# LPC82X_TSSOP_breadboard_mini.net
KiCad netlist of a schematic drawn in EAGLE
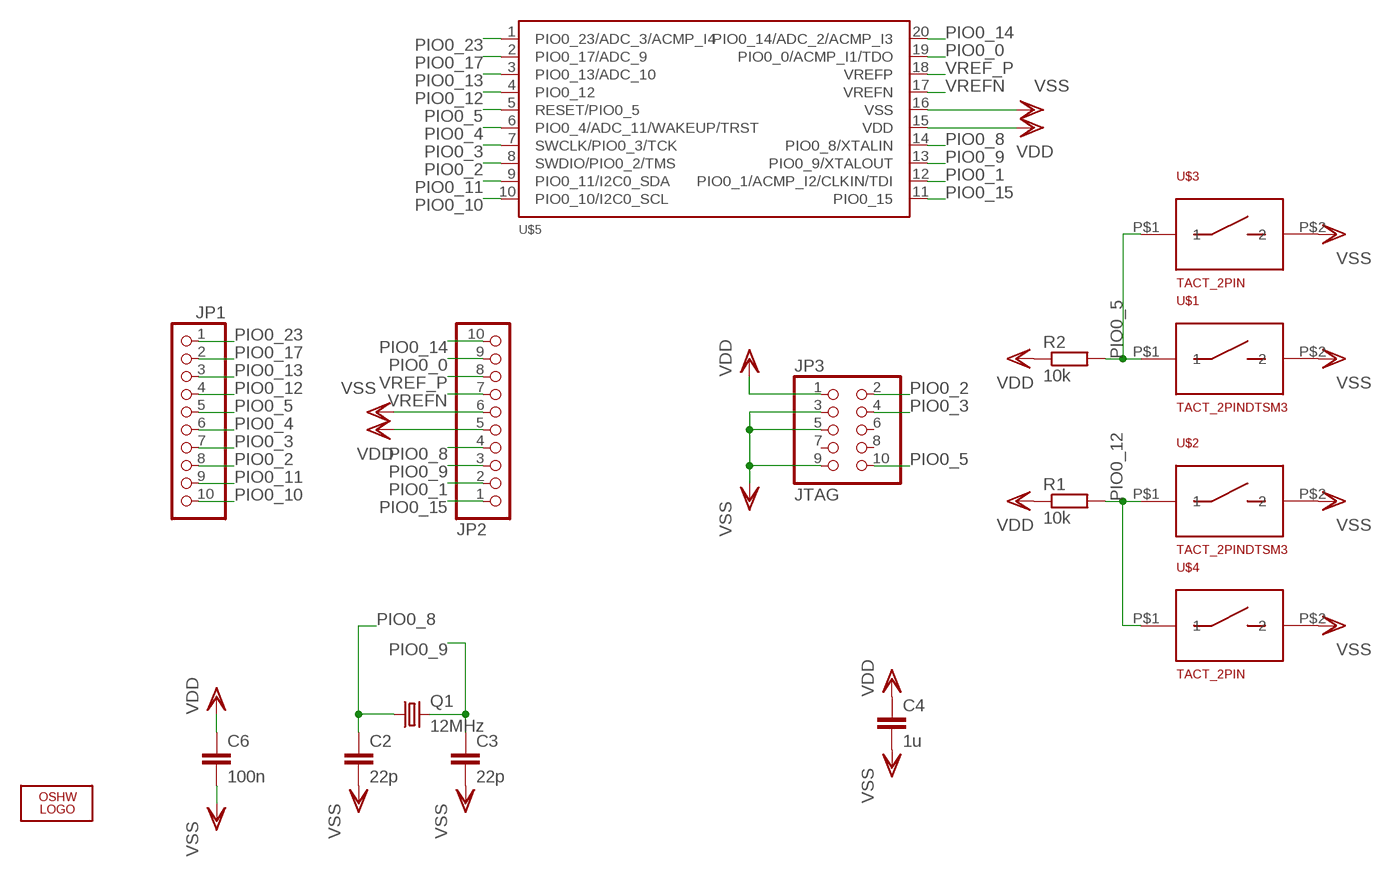
[diagram p0: schematic, sheet 1]

(export (version "E")
  (design (tool "Eeschema 10.0.6"))
  (components
    (comp (ref "C2")
      (value "22p")
      (footprint "eagle-import:C0603K")
      (libsource (lib "eagle-import") (part "C-EUC0603K"))
    )
    (comp (ref "C3")
      (value "22p")
      (footprint "eagle-import:C0603K")
      (libsource (lib "eagle-import") (part "C-EUC0603K"))
    )
    (comp (ref "C4")
      (value "1u")
      (footprint "eagle-import:C0805K")
      (libsource (lib "eagle-import") (part "bart_rcl_C-EUC0805K"))
    )
    (comp (ref "C6")
      (value "100n")
      (footprint "eagle-import:C0603K")
      (libsource (lib "eagle-import") (part "C-EUC0603K"))
    )
    (comp (ref "JP1")
      (value "PINHD-1X10NORM_OCT")
      (footprint "eagle-import:1X10_NORMAL_OCT")
      (libsource (lib "eagle-import") (part "PINHD-1X10NORM_OCT"))
    )
    (comp (ref "JP2")
      (value "PINHD-1X10NORM_OCT")
      (footprint "eagle-import:1X10_NORMAL_OCT")
      (libsource (lib "eagle-import") (part "PINHD-1X10NORM_OCT"))
    )
    (comp (ref "JP3")
      (value "JTAG")
      (footprint "eagle-import:2X05_1.27_SMD")
      (libsource (lib "eagle-import") (part "PINHD-2X5SMD_1.27_SMD"))
    )
    (comp (ref "LOGO2")
      (value "OSHW_LOGO_FILLX0150-NT")
      (footprint "eagle-import:OSHW_FILLX150_NOTEXT")
      (libsource (lib "eagle-import") (part "OSHW_LOGO_FILLX0150-NT"))
    )
    (comp (ref "Q1")
      (value "12MHz")
      (footprint "eagle-import:CRYSTAL_5.0X3.2")
      (libsource (lib "eagle-import") (part "CRYSTALSMD_5.0X3.2"))
    )
    (comp (ref "R1")
      (value "10k")
      (footprint "eagle-import:R0603")
      (libsource (lib "eagle-import") (part "R-EU_R0603"))
    )
    (comp (ref "R2")
      (value "10k")
      (footprint "eagle-import:R0603")
      (libsource (lib "eagle-import") (part "R-EU_R0603"))
    )
    (comp (ref "U$1")
      (value "TACT_2PINDTSM3")
      (footprint "eagle-import:DTSM3")
      (libsource (lib "eagle-import") (part "TACT_2PINDTSM3"))
    )
    (comp (ref "U$2")
      (value "TACT_2PINDTSM3")
      (footprint "eagle-import:DTSM3")
      (libsource (lib "eagle-import") (part "TACT_2PINDTSM3"))
    )
    (comp (ref "U$3")
      (value "TACT_2PIN")
      (footprint "eagle-import:TD-85XU")
      (libsource (lib "eagle-import") (part "TACT_2PIN"))
    )
    (comp (ref "U$4")
      (value "TACT_2PIN")
      (footprint "eagle-import:TD-85XU")
      (libsource (lib "eagle-import") (part "TACT_2PIN"))
    )
    (comp (ref "U$5")
      (value "LPC82XM101JDH20")
      (footprint "eagle-import:TSSOP20")
      (libsource (lib "eagle-import") (part "LPC82XM101JDH20"))
    )
  )
  (nets
    (net (code "1") (name "/PIO0_0") (class "Default")
      (node (ref "JP2") (pin "9") (pinfunction "9_9") (pintype "passive"))
      (node (ref "U$5") (pin "19") (pinfunction "PIO0_0/ACMP_I1/TDO_19") (pintype "bidirectional"))
    )
    (net (code "2") (name "/PIO0_1") (class "Default")
      (node (ref "JP2") (pin "2") (pinfunction "2_2") (pintype "passive"))
      (node (ref "U$5") (pin "12") (pinfunction "PIO0_1/ACMP_I2/CLKIN/TDI_12") (pintype "bidirectional"))
    )
    (net (code "3") (name "/PIO0_2") (class "Default")
      (node (ref "JP1") (pin "8") (pinfunction "8_8") (pintype "passive"))
      (node (ref "JP3") (pin "2") (pinfunction "2_2") (pintype "passive"))
      (node (ref "U$5") (pin "8") (pinfunction "SWDIO/PIO0_2/TMS_8") (pintype "bidirectional"))
    )
    (net (code "4") (name "/PIO0_3") (class "Default")
      (node (ref "JP1") (pin "7") (pinfunction "7_7") (pintype "passive"))
      (node (ref "JP3") (pin "4") (pinfunction "4_4") (pintype "passive"))
      (node (ref "U$5") (pin "7") (pinfunction "SWCLK/PIO0_3/TCK_7") (pintype "bidirectional"))
    )
    (net (code "5") (name "/PIO0_4") (class "Default")
      (node (ref "JP1") (pin "6") (pinfunction "6_6") (pintype "passive"))
      (node (ref "U$5") (pin "6") (pinfunction "PIO0_4/ADC_11/WAKEUP/TRST_6") (pintype "bidirectional"))
    )
    (net (code "6") (name "/PIO0_5") (class "Default")
      (node (ref "JP1") (pin "5") (pinfunction "5_5") (pintype "passive"))
      (node (ref "JP3") (pin "10") (pinfunction "10_10") (pintype "passive"))
      (node (ref "R2") (pin "2") (pinfunction "2_2") (pintype "passive"))
      (node (ref "U$1") (pin "P$1") (pinfunction "1_P$1") (pintype "bidirectional"))
      (node (ref "U$3") (pin "P$1") (pinfunction "1_P$1") (pintype "bidirectional"))
      (node (ref "U$5") (pin "5") (pinfunction "RESET/PIO0_5_5") (pintype "bidirectional"))
    )
    (net (code "7") (name "/PIO0_8") (class "Default")
      (node (ref "C2") (pin "1") (pinfunction "1_1") (pintype "passive"))
      (node (ref "JP2") (pin "4") (pinfunction "4_4") (pintype "passive"))
      (node (ref "Q1") (pin "1") (pinfunction "1_1") (pintype "passive"))
      (node (ref "U$5") (pin "14") (pinfunction "PIO0_8/XTALIN_14") (pintype "bidirectional"))
    )
    (net (code "8") (name "/PIO0_9") (class "Default")
      (node (ref "C3") (pin "1") (pinfunction "1_1") (pintype "passive"))
      (node (ref "JP2") (pin "3") (pinfunction "3_3") (pintype "passive"))
      (node (ref "Q1") (pin "2") (pinfunction "2_2") (pintype "passive"))
      (node (ref "U$5") (pin "13") (pinfunction "PIO0_9/XTALOUT_13") (pintype "bidirectional"))
    )
    (net (code "9") (name "/PIO0_10") (class "Default")
      (node (ref "JP1") (pin "10") (pinfunction "10_10") (pintype "passive"))
      (node (ref "U$5") (pin "10") (pinfunction "PIO0_10/I2C0_SCL_10") (pintype "bidirectional"))
    )
    (net (code "10") (name "/PIO0_11") (class "Default")
      (node (ref "JP1") (pin "9") (pinfunction "9_9") (pintype "passive"))
      (node (ref "U$5") (pin "9") (pinfunction "PIO0_11/I2C0_SDA_9") (pintype "bidirectional"))
    )
    (net (code "11") (name "/PIO0_12") (class "Default")
      (node (ref "JP1") (pin "4") (pinfunction "4_4") (pintype "passive"))
      (node (ref "R1") (pin "2") (pinfunction "2_2") (pintype "passive"))
      (node (ref "U$2") (pin "P$1") (pinfunction "1_P$1") (pintype "bidirectional"))
      (node (ref "U$4") (pin "P$1") (pinfunction "1_P$1") (pintype "bidirectional"))
      (node (ref "U$5") (pin "4") (pinfunction "PIO0_12_4") (pintype "bidirectional"))
    )
    (net (code "12") (name "/PIO0_13") (class "Default")
      (node (ref "JP1") (pin "3") (pinfunction "3_3") (pintype "passive"))
      (node (ref "U$5") (pin "3") (pinfunction "PIO0_13/ADC_10_3") (pintype "bidirectional"))
    )
    (net (code "13") (name "/PIO0_14") (class "Default")
      (node (ref "JP2") (pin "10") (pinfunction "10_10") (pintype "passive"))
      (node (ref "U$5") (pin "20") (pinfunction "PIO0_14/ADC_2/ACMP_I3_20") (pintype "bidirectional"))
    )
    (net (code "14") (name "/PIO0_15") (class "Default")
      (node (ref "JP2") (pin "1") (pinfunction "1_1") (pintype "passive"))
      (node (ref "U$5") (pin "11") (pinfunction "PIO0_15_11") (pintype "bidirectional"))
    )
    (net (code "15") (name "/PIO0_17") (class "Default")
      (node (ref "JP1") (pin "2") (pinfunction "2_2") (pintype "passive"))
      (node (ref "U$5") (pin "2") (pinfunction "PIO0_17/ADC_9_2") (pintype "bidirectional"))
    )
    (net (code "16") (name "/PIO0_23") (class "Default")
      (node (ref "JP1") (pin "1") (pinfunction "1_1") (pintype "passive"))
      (node (ref "U$5") (pin "1") (pinfunction "PIO0_23/ADC_3/ACMP_I4_1") (pintype "bidirectional"))
    )
    (net (code "17") (name "/VREFN") (class "Default")
      (node (ref "JP2") (pin "7") (pinfunction "7_7") (pintype "passive"))
      (node (ref "U$5") (pin "17") (pinfunction "VREFN_17") (pintype "bidirectional"))
    )
    (net (code "18") (name "/VREF_P") (class "Default")
      (node (ref "JP2") (pin "8") (pinfunction "8_8") (pintype "passive"))
      (node (ref "U$5") (pin "18") (pinfunction "VREFP_18") (pintype "bidirectional"))
    )
    (net (code "19") (name "VDD") (class "Default")
      (node (ref "C4") (pin "1") (pinfunction "1_1") (pintype "passive"))
      (node (ref "C6") (pin "1") (pinfunction "1_1") (pintype "passive"))
      (node (ref "JP2") (pin "5") (pinfunction "5_5") (pintype "passive"))
      (node (ref "JP3") (pin "1") (pinfunction "1_1") (pintype "passive"))
      (node (ref "R1") (pin "1") (pinfunction "1_1") (pintype "passive"))
      (node (ref "R2") (pin "1") (pinfunction "1_1") (pintype "passive"))
      (node (ref "U$5") (pin "15") (pinfunction "VDD_15") (pintype "bidirectional"))
    )
    (net (code "20") (name "VSS") (class "Default")
      (node (ref "C2") (pin "2") (pinfunction "2_2") (pintype "passive"))
      (node (ref "C3") (pin "2") (pinfunction "2_2") (pintype "passive"))
      (node (ref "C4") (pin "2") (pinfunction "2_2") (pintype "passive"))
      (node (ref "C6") (pin "2") (pinfunction "2_2") (pintype "passive"))
      (node (ref "JP2") (pin "6") (pinfunction "6_6") (pintype "passive"))
      (node (ref "JP3") (pin "3") (pinfunction "3_3") (pintype "passive"))
      (node (ref "JP3") (pin "5") (pinfunction "5_5") (pintype "passive"))
      (node (ref "JP3") (pin "9") (pinfunction "9_9") (pintype "passive"))
      (node (ref "U$1") (pin "P$2") (pinfunction "2_P$2") (pintype "bidirectional"))
      (node (ref "U$2") (pin "P$2") (pinfunction "2_P$2") (pintype "bidirectional"))
      (node (ref "U$3") (pin "P$2") (pinfunction "2_P$2") (pintype "bidirectional"))
      (node (ref "U$4") (pin "P$2") (pinfunction "2_P$2") (pintype "bidirectional"))
      (node (ref "U$5") (pin "16") (pinfunction "VSS_16") (pintype "bidirectional"))
    )
    (net (code "21") (name "unconnected-(JP3-Pad6)") (class "Default")
      (node (ref "JP3") (pin "6") (pinfunction "6_6") (pintype "passive"))
    )
    (net (code "22") (name "unconnected-(JP3-Pad7)") (class "Default")
      (node (ref "JP3") (pin "7") (pinfunction "7_7") (pintype "passive"))
    )
    (net (code "23") (name "unconnected-(JP3-Pad8)") (class "Default")
      (node (ref "JP3") (pin "8") (pinfunction "8_8") (pintype "passive"))
    )
  )
)
